# Fuente_Conn.net
KiCad netlist of a schematic drawn in Altium Designer
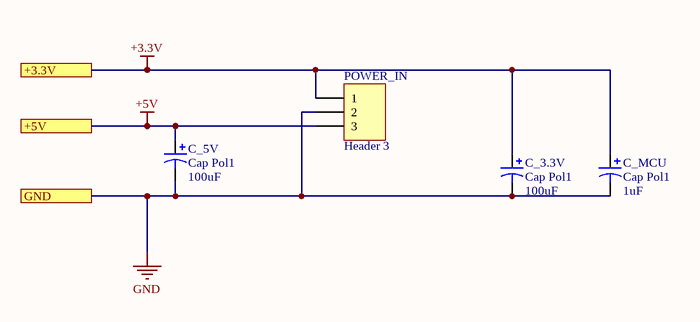
[diagram p0: Fuente_Conn.SchDoc]

(export (version "E")
  (design (tool "Eeschema 10.0.6"))
  (components
    (comp (ref "C_3.3V")
      (value "Cap Pol1")
      (footprint "CAPR5-4X5")
      (description "Polarized Capacitor (Radial)")
      (fields (field (name "ALTIUM_VALUE") "100uF") (field (name "PUBLISHER") "Altium Limited"))
      (libsource (lib "Miscellaneous Devices") (part "Cap Pol1"))
    )
    (comp (ref "C_5V")
      (value "Cap Pol1")
      (footprint "CAPR5-4X5")
      (description "Polarized Capacitor (Radial)")
      (fields (field (name "ALTIUM_VALUE") "100uF") (field (name "PUBLISHER") "Altium Limited"))
      (libsource (lib "Miscellaneous Devices") (part "Cap Pol1"))
    )
    (comp (ref "C_MCU")
      (value "Cap Pol1")
      (footprint "CAPR5-4X5")
      (description "Polarized Capacitor (Radial)")
      (fields (field (name "ALTIUM_VALUE") "1uF") (field (name "PUBLISHER") "Altium Limited"))
      (libsource (lib "Miscellaneous Devices") (part "Cap Pol1"))
    )
    (comp (ref "POWER_IN")
      (value "Header 3")
      (footprint "HDR1X3")
      (description "Header, 3-Pin")
      (fields (field (name "PUBLISHER") "Altium Limited"))
      (libsource (lib "Miscellaneous Connectors") (part "Header 3"))
    )
  )
  (nets
    (net (code "1") (name "+3.3V") (class "Default")
      (node (ref "C_3.3V") (pin "1") (pinfunction "1_1") (pintype "passive"))
      (node (ref "C_MCU") (pin "1") (pinfunction "1_1") (pintype "passive"))
      (node (ref "POWER_IN") (pin "1") (pinfunction "1_1") (pintype "passive"))
    )
    (net (code "2") (name "+5V") (class "Default")
      (node (ref "C_5V") (pin "1") (pinfunction "1_1") (pintype "passive"))
      (node (ref "POWER_IN") (pin "3") (pinfunction "3_3") (pintype "passive"))
    )
    (net (code "3") (name "GND") (class "Default")
      (node (ref "C_3.3V") (pin "2") (pinfunction "2_2") (pintype "passive"))
      (node (ref "C_5V") (pin "2") (pinfunction "2_2") (pintype "passive"))
      (node (ref "C_MCU") (pin "2") (pinfunction "2_2") (pintype "passive"))
      (node (ref "POWER_IN") (pin "2") (pinfunction "2_2") (pintype "passive"))
    )
  )
)
